# ENC_SENSOR.net
KiCad netlist of a schematic drawn in Altium Designer
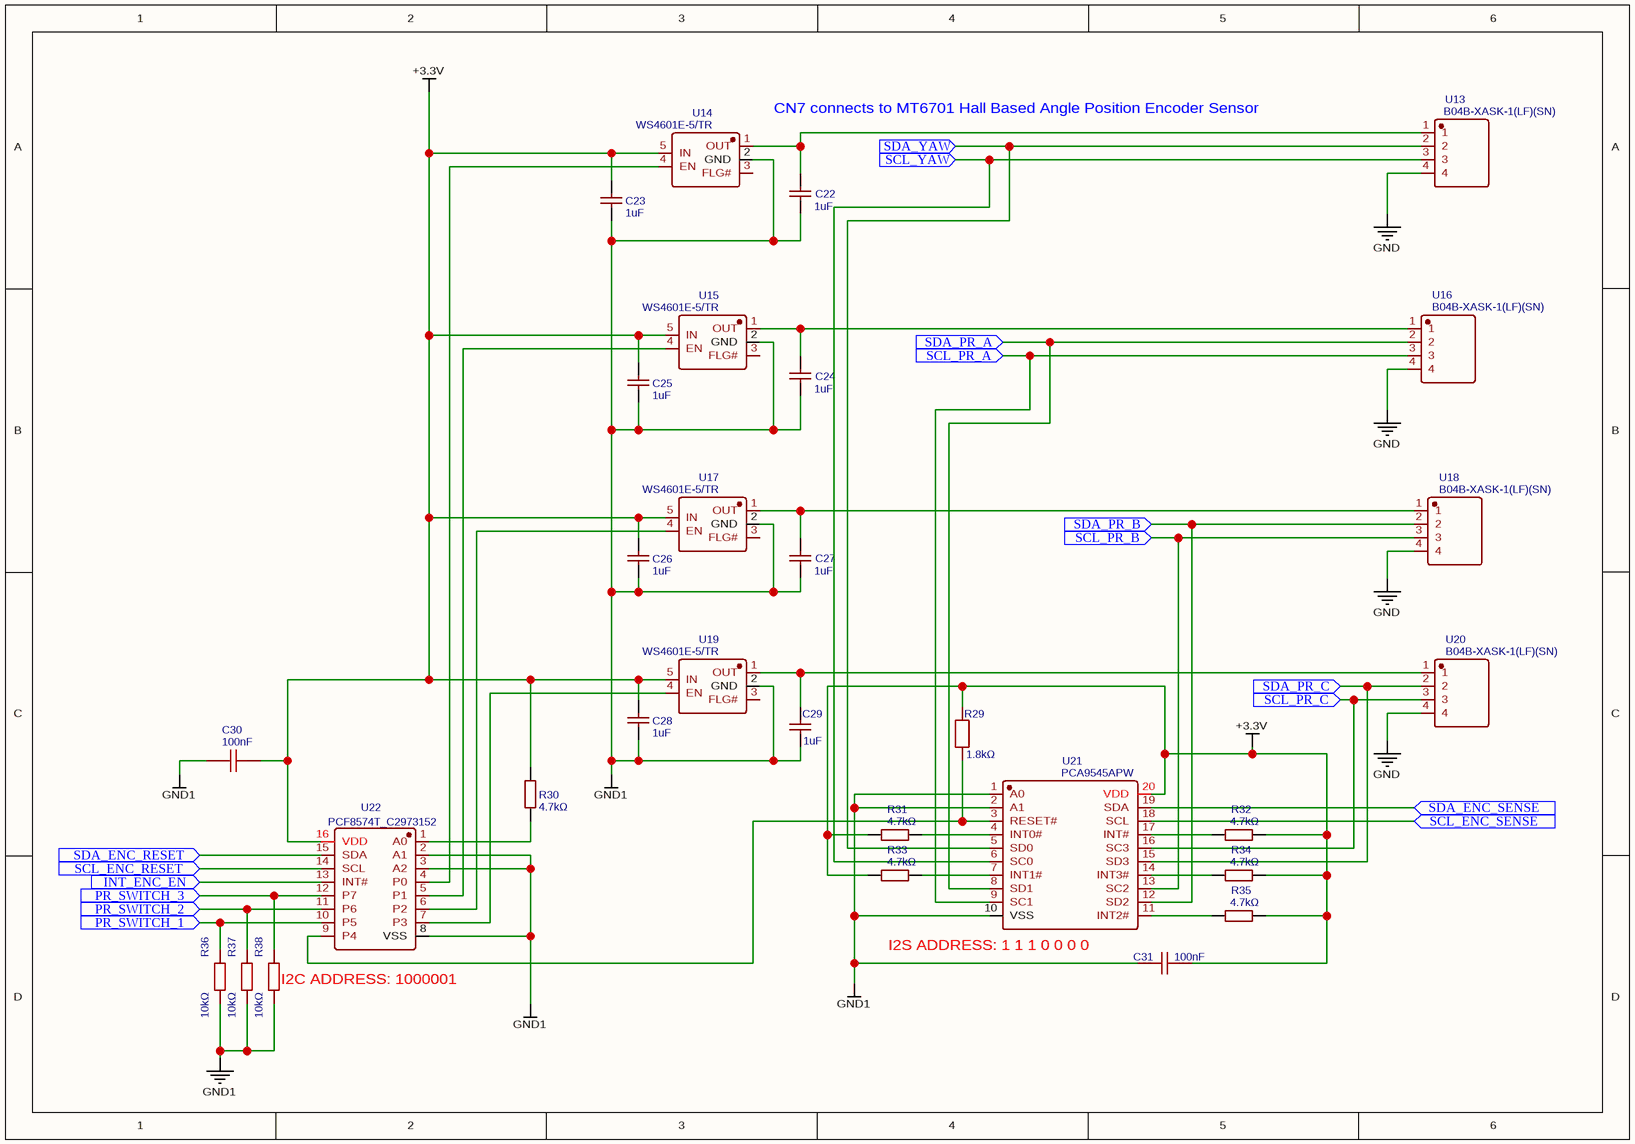
[diagram p0: ENC_SENSOR.schdoc]

(export (version "E")
  (design (tool "Eeschema 10.0.6"))
  (components
    (comp (ref "C22")
      (value "1uF")
      (fields
        (field (name "BOM_MANUFACTURER PART") "CC1206KKX7R8BB105")
        (field (name "BOM_SUPPLIER PART") "C107184")
      )
      (libsource (lib "altium-import") (part "root_1_1uF_"))
    )
    (comp (ref "C23")
      (value "1uF")
      (fields
        (field (name "BOM_MANUFACTURER PART") "CC1206KKX7R8BB105")
        (field (name "BOM_SUPPLIER PART") "C107184")
      )
      (libsource (lib "altium-import") (part "root_3_1uF_"))
    )
    (comp (ref "C24")
      (value "1uF")
      (fields
        (field (name "BOM_MANUFACTURER PART") "CC1206KKX7R8BB105")
        (field (name "BOM_SUPPLIER PART") "C107184")
      )
      (libsource (lib "altium-import") (part "root_1_1uF_"))
    )
    (comp (ref "C25")
      (value "1uF")
      (fields
        (field (name "BOM_MANUFACTURER PART") "CC1206KKX7R8BB105")
        (field (name "BOM_SUPPLIER PART") "C107184")
      )
      (libsource (lib "altium-import") (part "root_3_1uF_"))
    )
    (comp (ref "C26")
      (value "1uF")
      (fields
        (field (name "BOM_MANUFACTURER PART") "CC1206KKX7R8BB105")
        (field (name "BOM_SUPPLIER PART") "C107184")
      )
      (libsource (lib "altium-import") (part "root_3_1uF_"))
    )
    (comp (ref "C27")
      (value "1uF")
      (fields
        (field (name "BOM_MANUFACTURER PART") "CC1206KKX7R8BB105")
        (field (name "BOM_SUPPLIER PART") "C107184")
      )
      (libsource (lib "altium-import") (part "root_1_1uF_"))
    )
    (comp (ref "C28")
      (value "1uF")
      (fields
        (field (name "BOM_MANUFACTURER PART") "CC1206KKX7R8BB105")
        (field (name "BOM_SUPPLIER PART") "C107184")
      )
      (libsource (lib "altium-import") (part "root_3_1uF_"))
    )
    (comp (ref "C29")
      (value "1uF")
      (fields
        (field (name "BOM_MANUFACTURER PART") "CC1206KKX7R8BB105")
        (field (name "BOM_SUPPLIER PART") "C107184")
      )
      (libsource (lib "altium-import") (part "root_1_1uF_"))
    )
    (comp (ref "C30")
      (value "100nF")
      (fields
        (field (name "BOM_SUPPLIER PART") "C519981")
        (field (name "BOM_MANUFACTURER PART") "CC0805KRX7R8BB104")
        (field (name "CONTRIBUTOR") "LCSC")
      )
      (libsource (lib "altium-import") (part "root_2_100nF_"))
    )
    (comp (ref "C31")
      (value "100nF")
      (fields
        (field (name "BOM_SUPPLIER PART") "C519981")
        (field (name "BOM_MANUFACTURER PART") "CC0805KRX7R8BB104")
        (field (name "CONTRIBUTOR") "LCSC")
      )
      (libsource (lib "altium-import") (part "root_2_100nF_"))
    )
    (comp (ref "R29")
      (value "1.8kΩ")
      (fields
        (field (name "BOM_SUPPLIER PART") "C513603")
        (field (name "BOM_MANUFACTURER PART") "RT0805BRE071K8L")
        (field (name "CONTRIBUTOR") "LCSC")
      )
      (libsource (lib "altium-import") (part "root_1_1.8kΩ_"))
    )
    (comp (ref "R30")
      (value "4.7kΩ")
      (fields
        (field (name "BOM_MANUFACTURER PART") "0805W8J0472T5E")
        (field (name "BOM_SUPPLIER PART") "C26022")
      )
      (libsource (lib "altium-import") (part "root_1_4.7kΩ_"))
    )
    (comp (ref "R31")
      (value "4.7kΩ")
      (fields
        (field (name "BOM_MANUFACTURER PART") "0805W8J0472T5E")
        (field (name "BOM_SUPPLIER PART") "C26022")
      )
      (libsource (lib "altium-import") (part "root_0_4.7kΩ_"))
    )
    (comp (ref "R32")
      (value "4.7kΩ")
      (fields
        (field (name "BOM_MANUFACTURER PART") "0805W8J0472T5E")
        (field (name "BOM_SUPPLIER PART") "C26022")
      )
      (libsource (lib "altium-import") (part "root_0_4.7kΩ_"))
    )
    (comp (ref "R33")
      (value "4.7kΩ")
      (fields
        (field (name "BOM_MANUFACTURER PART") "0805W8J0472T5E")
        (field (name "BOM_SUPPLIER PART") "C26022")
      )
      (libsource (lib "altium-import") (part "root_0_4.7kΩ_"))
    )
    (comp (ref "R34")
      (value "4.7kΩ")
      (fields
        (field (name "BOM_MANUFACTURER PART") "0805W8J0472T5E")
        (field (name "BOM_SUPPLIER PART") "C26022")
      )
      (libsource (lib "altium-import") (part "root_0_4.7kΩ_"))
    )
    (comp (ref "R35")
      (value "4.7kΩ")
      (fields
        (field (name "BOM_MANUFACTURER PART") "0805W8J0472T5E")
        (field (name "BOM_SUPPLIER PART") "C26022")
      )
      (libsource (lib "altium-import") (part "root_0_4.7kΩ_"))
    )
    (comp (ref "R36")
      (value "10kΩ")
      (fields
        (field (name "BOM_SUPPLIER PART") "C332266")
        (field (name "BOM_MANUFACTURER PART") "TR0805D10KP0550")
        (field (name "CONTRIBUTOR") "LCSC")
      )
      (libsource (lib "altium-import") (part "root_1_10kΩ_"))
    )
    (comp (ref "R37")
      (value "10kΩ")
      (fields
        (field (name "BOM_SUPPLIER PART") "C332266")
        (field (name "BOM_MANUFACTURER PART") "TR0805D10KP0550")
        (field (name "CONTRIBUTOR") "LCSC")
      )
      (libsource (lib "altium-import") (part "root_1_10kΩ_"))
    )
    (comp (ref "R38")
      (value "10kΩ")
      (fields
        (field (name "BOM_SUPPLIER PART") "C332266")
        (field (name "BOM_MANUFACTURER PART") "TR0805D10KP0550")
        (field (name "CONTRIBUTOR") "LCSC")
      )
      (libsource (lib "altium-import") (part "root_1_10kΩ_"))
    )
    (comp (ref "U13")
      (value "B04B-XASK-1(LF)(SN)")
      (fields (field (name "BOM_SUPPLIER PART") "C264994") (field (name "CONTRIBUTOR") "LCSC"))
      (libsource (lib "altium-import") (part "root_0_B04B-XASK-1(LF)(SN)_"))
    )
    (comp (ref "U14")
      (value "WS4601E-5/TR")
      (fields (field (name "BOM_SUPPLIER PART") "C213171") (field (name "CONTRIBUTOR") "LCSC"))
      (libsource (lib "altium-import") (part "root_0_WS4601E-5/TR_"))
    )
    (comp (ref "U15")
      (value "WS4601E-5/TR")
      (fields (field (name "BOM_SUPPLIER PART") "C213171") (field (name "CONTRIBUTOR") "LCSC"))
      (libsource (lib "altium-import") (part "root_0_WS4601E-5/TR_"))
    )
    (comp (ref "U16")
      (value "B04B-XASK-1(LF)(SN)")
      (fields (field (name "BOM_SUPPLIER PART") "C264994") (field (name "CONTRIBUTOR") "LCSC"))
      (libsource (lib "altium-import") (part "root_0_B04B-XASK-1(LF)(SN)_"))
    )
    (comp (ref "U17")
      (value "WS4601E-5/TR")
      (fields (field (name "BOM_SUPPLIER PART") "C213171") (field (name "CONTRIBUTOR") "LCSC"))
      (libsource (lib "altium-import") (part "root_0_WS4601E-5/TR_"))
    )
    (comp (ref "U18")
      (value "B04B-XASK-1(LF)(SN)")
      (fields (field (name "BOM_SUPPLIER PART") "C264994") (field (name "CONTRIBUTOR") "LCSC"))
      (libsource (lib "altium-import") (part "root_0_B04B-XASK-1(LF)(SN)_"))
    )
    (comp (ref "U19")
      (value "WS4601E-5/TR")
      (fields (field (name "BOM_SUPPLIER PART") "C213171") (field (name "CONTRIBUTOR") "LCSC"))
      (libsource (lib "altium-import") (part "root_0_WS4601E-5/TR_"))
    )
    (comp (ref "U20")
      (value "B04B-XASK-1(LF)(SN)")
      (fields (field (name "BOM_SUPPLIER PART") "C264994") (field (name "CONTRIBUTOR") "LCSC"))
      (libsource (lib "altium-import") (part "root_0_B04B-XASK-1(LF)(SN)_"))
    )
    (comp (ref "U21")
      (value "PCA9545APW")
      (fields (field (name "BOM_SUPPLIER PART") "C129515") (field (name "CONTRIBUTOR") "LCSC"))
      (libsource (lib "altium-import") (part "root_0_PCA9545APW_"))
    )
    (comp (ref "U22")
      (value "PCF8574T_C2973152")
      (fields
        (field (name "BOM_SUPPLIER PART") "C7605")
        (field (name "BOM_MANUFACTURER PART") "PCF8574T/3,518")
        (field (name "CONTRIBUTOR") "LCSC")
      )
      (libsource (lib "altium-import") (part "root_0_PCF8574T_C2973152_"))
    )
  )
  (nets
    (net (code "1") (name "+3.3V") (class "Default")
      (node (ref "C23") (pin "1") (pinfunction "1_1") (pintype "passive"))
      (node (ref "C25") (pin "1") (pinfunction "1_1") (pintype "passive"))
      (node (ref "C26") (pin "1") (pinfunction "1_1") (pintype "passive"))
      (node (ref "C28") (pin "1") (pinfunction "1_1") (pintype "passive"))
      (node (ref "C30") (pin "1") (pinfunction "1_1") (pintype "passive"))
      (node (ref "C31") (pin "1") (pinfunction "1_1") (pintype "passive"))
      (node (ref "R29") (pin "2") (pinfunction "2_2") (pintype "passive"))
      (node (ref "R30") (pin "2") (pinfunction "2_2") (pintype "passive"))
      (node (ref "R31") (pin "1") (pinfunction "1_1") (pintype "passive"))
      (node (ref "R32") (pin "2") (pinfunction "2_2") (pintype "passive"))
      (node (ref "R33") (pin "1") (pinfunction "1_1") (pintype "passive"))
      (node (ref "R34") (pin "2") (pinfunction "2_2") (pintype "passive"))
      (node (ref "R35") (pin "2") (pinfunction "2_2") (pintype "passive"))
      (node (ref "U14") (pin "5") (pinfunction "IN_5") (pintype "passive"))
      (node (ref "U15") (pin "5") (pinfunction "IN_5") (pintype "passive"))
      (node (ref "U17") (pin "5") (pinfunction "IN_5") (pintype "passive"))
      (node (ref "U19") (pin "5") (pinfunction "IN_5") (pintype "passive"))
      (node (ref "U21") (pin "20") (pinfunction "VDD_20") (pintype "passive"))
      (node (ref "U22") (pin "16") (pinfunction "VDD_16") (pintype "passive"))
    )
    (net (code "2") (name "/INT_ENC_EN") (class "Default")
      (node (ref "U22") (pin "13") (pinfunction "INT#_13") (pintype "passive"))
    )
    (net (code "3") (name "/PR_SWITCH_1") (class "Default")
      (node (ref "R36") (pin "2") (pinfunction "2_2") (pintype "passive"))
      (node (ref "U22") (pin "10") (pinfunction "P5_10") (pintype "passive"))
    )
    (net (code "4") (name "/PR_SWITCH_2") (class "Default")
      (node (ref "R37") (pin "2") (pinfunction "2_2") (pintype "passive"))
      (node (ref "U22") (pin "11") (pinfunction "P6_11") (pintype "passive"))
    )
    (net (code "5") (name "/PR_SWITCH_3") (class "Default")
      (node (ref "R38") (pin "2") (pinfunction "2_2") (pintype "passive"))
      (node (ref "U22") (pin "12") (pinfunction "P7_12") (pintype "passive"))
    )
    (net (code "6") (name "/SCL_ENC_RESET") (class "Default")
      (node (ref "U22") (pin "14") (pinfunction "SCL_14") (pintype "passive"))
    )
    (net (code "7") (name "/SCL_ENC_SENSE") (class "Default")
      (node (ref "U21") (pin "18") (pinfunction "SCL_18") (pintype "passive"))
    )
    (net (code "8") (name "/SCL_PR_A") (class "Default")
      (node (ref "U16") (pin "3") (pinfunction "3_3") (pintype "passive"))
      (node (ref "U21") (pin "9") (pinfunction "SC1_9") (pintype "passive"))
    )
    (net (code "9") (name "/SCL_PR_B") (class "Default")
      (node (ref "U18") (pin "3") (pinfunction "3_3") (pintype "passive"))
      (node (ref "U21") (pin "13") (pinfunction "SC2_13") (pintype "passive"))
    )
    (net (code "10") (name "/SCL_PR_C") (class "Default")
      (node (ref "U20") (pin "3") (pinfunction "3_3") (pintype "passive"))
      (node (ref "U21") (pin "16") (pinfunction "SC3_16") (pintype "passive"))
    )
    (net (code "11") (name "/SCL_YAW") (class "Default")
      (node (ref "U13") (pin "3") (pinfunction "3_3") (pintype "passive"))
      (node (ref "U21") (pin "6") (pinfunction "SC0_6") (pintype "passive"))
    )
    (net (code "12") (name "/SDA_ENC_RESET") (class "Default")
      (node (ref "U22") (pin "15") (pinfunction "SDA_15") (pintype "passive"))
    )
    (net (code "13") (name "/SDA_ENC_SENSE") (class "Default")
      (node (ref "U21") (pin "19") (pinfunction "SDA_19") (pintype "passive"))
    )
    (net (code "14") (name "/SDA_PR_A") (class "Default")
      (node (ref "U16") (pin "2") (pinfunction "2_2") (pintype "passive"))
      (node (ref "U21") (pin "8") (pinfunction "SD1_8") (pintype "passive"))
    )
    (net (code "15") (name "/SDA_PR_B") (class "Default")
      (node (ref "U18") (pin "2") (pinfunction "2_2") (pintype "passive"))
      (node (ref "U21") (pin "12") (pinfunction "SD2_12") (pintype "passive"))
    )
    (net (code "16") (name "/SDA_PR_C") (class "Default")
      (node (ref "U20") (pin "2") (pinfunction "2_2") (pintype "passive"))
      (node (ref "U21") (pin "15") (pinfunction "SD3_15") (pintype "passive"))
    )
    (net (code "17") (name "/SDA_YAW") (class "Default")
      (node (ref "U13") (pin "2") (pinfunction "2_2") (pintype "passive"))
      (node (ref "U21") (pin "5") (pinfunction "SD0_5") (pintype "passive"))
    )
    (net (code "18") (name "GND") (class "Default")
      (node (ref "U13") (pin "4") (pinfunction "4_4") (pintype "passive"))
      (node (ref "U16") (pin "4") (pinfunction "4_4") (pintype "passive"))
      (node (ref "U18") (pin "4") (pinfunction "4_4") (pintype "passive"))
      (node (ref "U20") (pin "4") (pinfunction "4_4") (pintype "passive"))
    )
    (net (code "19") (name "GND1") (class "Default")
      (node (ref "C22") (pin "1") (pinfunction "1_1") (pintype "passive"))
      (node (ref "C23") (pin "2") (pinfunction "2_2") (pintype "passive"))
      (node (ref "C24") (pin "1") (pinfunction "1_1") (pintype "passive"))
      (node (ref "C25") (pin "2") (pinfunction "2_2") (pintype "passive"))
      (node (ref "C26") (pin "2") (pinfunction "2_2") (pintype "passive"))
      (node (ref "C27") (pin "1") (pinfunction "1_1") (pintype "passive"))
      (node (ref "C28") (pin "2") (pinfunction "2_2") (pintype "passive"))
      (node (ref "C29") (pin "1") (pinfunction "1_1") (pintype "passive"))
      (node (ref "C30") (pin "2") (pinfunction "2_2") (pintype "passive"))
      (node (ref "C31") (pin "2") (pinfunction "2_2") (pintype "passive"))
      (node (ref "R36") (pin "1") (pinfunction "1_1") (pintype "passive"))
      (node (ref "R37") (pin "1") (pinfunction "1_1") (pintype "passive"))
      (node (ref "R38") (pin "1") (pinfunction "1_1") (pintype "passive"))
      (node (ref "U14") (pin "2") (pinfunction "GND_2") (pintype "passive"))
      (node (ref "U15") (pin "2") (pinfunction "GND_2") (pintype "passive"))
      (node (ref "U17") (pin "2") (pinfunction "GND_2") (pintype "passive"))
      (node (ref "U19") (pin "2") (pinfunction "GND_2") (pintype "passive"))
      (node (ref "U21") (pin "1") (pinfunction "A0_1") (pintype "passive"))
      (node (ref "U21") (pin "10") (pinfunction "VSS_10") (pintype "passive"))
      (node (ref "U21") (pin "2") (pinfunction "A1_2") (pintype "passive"))
      (node (ref "U22") (pin "2") (pinfunction "A1_2") (pintype "passive"))
      (node (ref "U22") (pin "3") (pinfunction "A2_3") (pintype "passive"))
      (node (ref "U22") (pin "8") (pinfunction "VSS_8") (pintype "passive"))
    )
    (net (code "20") (name "Net-(U14-EN)") (class "Default")
      (node (ref "U14") (pin "4") (pinfunction "EN_4") (pintype "passive"))
      (node (ref "U22") (pin "4") (pinfunction "P0_4") (pintype "passive"))
    )
    (net (code "21") (name "Net-(U14-OUT)") (class "Default")
      (node (ref "C22") (pin "2") (pinfunction "2_2") (pintype "passive"))
      (node (ref "U13") (pin "1") (pinfunction "1_1") (pintype "passive"))
      (node (ref "U14") (pin "1") (pinfunction "OUT_1") (pintype "passive"))
    )
    (net (code "22") (name "Net-(U15-EN)") (class "Default")
      (node (ref "U15") (pin "4") (pinfunction "EN_4") (pintype "passive"))
      (node (ref "U22") (pin "5") (pinfunction "P1_5") (pintype "passive"))
    )
    (net (code "23") (name "Net-(U15-OUT)") (class "Default")
      (node (ref "C24") (pin "2") (pinfunction "2_2") (pintype "passive"))
      (node (ref "U15") (pin "1") (pinfunction "OUT_1") (pintype "passive"))
      (node (ref "U16") (pin "1") (pinfunction "1_1") (pintype "passive"))
    )
    (net (code "24") (name "Net-(U17-EN)") (class "Default")
      (node (ref "U17") (pin "4") (pinfunction "EN_4") (pintype "passive"))
      (node (ref "U22") (pin "6") (pinfunction "P2_6") (pintype "passive"))
    )
    (net (code "25") (name "Net-(U17-OUT)") (class "Default")
      (node (ref "C27") (pin "2") (pinfunction "2_2") (pintype "passive"))
      (node (ref "U17") (pin "1") (pinfunction "OUT_1") (pintype "passive"))
      (node (ref "U18") (pin "1") (pinfunction "1_1") (pintype "passive"))
    )
    (net (code "26") (name "Net-(U19-EN)") (class "Default")
      (node (ref "U19") (pin "4") (pinfunction "EN_4") (pintype "passive"))
      (node (ref "U22") (pin "7") (pinfunction "P3_7") (pintype "passive"))
    )
    (net (code "27") (name "Net-(U19-OUT)") (class "Default")
      (node (ref "C29") (pin "2") (pinfunction "2_2") (pintype "passive"))
      (node (ref "U19") (pin "1") (pinfunction "OUT_1") (pintype "passive"))
      (node (ref "U20") (pin "1") (pinfunction "1_1") (pintype "passive"))
    )
    (net (code "28") (name "Net-(U21-INT#)") (class "Default")
      (node (ref "R32") (pin "1") (pinfunction "1_1") (pintype "passive"))
      (node (ref "U21") (pin "17") (pinfunction "INT#_17") (pintype "passive"))
    )
    (net (code "29") (name "Net-(U21-INT0#)") (class "Default")
      (node (ref "R31") (pin "2") (pinfunction "2_2") (pintype "passive"))
      (node (ref "U21") (pin "4") (pinfunction "INT0#_4") (pintype "passive"))
    )
    (net (code "30") (name "Net-(U21-INT1#)") (class "Default")
      (node (ref "R33") (pin "2") (pinfunction "2_2") (pintype "passive"))
      (node (ref "U21") (pin "7") (pinfunction "INT1#_7") (pintype "passive"))
    )
    (net (code "31") (name "Net-(U21-INT2#)") (class "Default")
      (node (ref "R35") (pin "1") (pinfunction "1_1") (pintype "passive"))
      (node (ref "U21") (pin "11") (pinfunction "INT2#_11") (pintype "passive"))
    )
    (net (code "32") (name "Net-(U21-INT3#)") (class "Default")
      (node (ref "R34") (pin "1") (pinfunction "1_1") (pintype "passive"))
      (node (ref "U21") (pin "14") (pinfunction "INT3#_14") (pintype "passive"))
    )
    (net (code "33") (name "Net-(U21-RESET#)") (class "Default")
      (node (ref "R29") (pin "1") (pinfunction "1_1") (pintype "passive"))
      (node (ref "U21") (pin "3") (pinfunction "RESET#_3") (pintype "passive"))
      (node (ref "U22") (pin "9") (pinfunction "P4_9") (pintype "passive"))
    )
    (net (code "34") (name "Net-(U22-A0)") (class "Default")
      (node (ref "R30") (pin "1") (pinfunction "1_1") (pintype "passive"))
      (node (ref "U22") (pin "1") (pinfunction "A0_1") (pintype "passive"))
    )
    (net (code "35") (name "unconnected-(U14-FLG#-Pad3)") (class "Default")
      (node (ref "U14") (pin "3") (pinfunction "FLG#_3") (pintype "passive"))
    )
    (net (code "36") (name "unconnected-(U15-FLG#-Pad3)") (class "Default")
      (node (ref "U15") (pin "3") (pinfunction "FLG#_3") (pintype "passive"))
    )
    (net (code "37") (name "unconnected-(U17-FLG#-Pad3)") (class "Default")
      (node (ref "U17") (pin "3") (pinfunction "FLG#_3") (pintype "passive"))
    )
    (net (code "38") (name "unconnected-(U19-FLG#-Pad3)") (class "Default")
      (node (ref "U19") (pin "3") (pinfunction "FLG#_3") (pintype "passive"))
    )
  )
)
